# 15_-CLOCK.net
KiCad netlist of a schematic drawn in Altium Designer
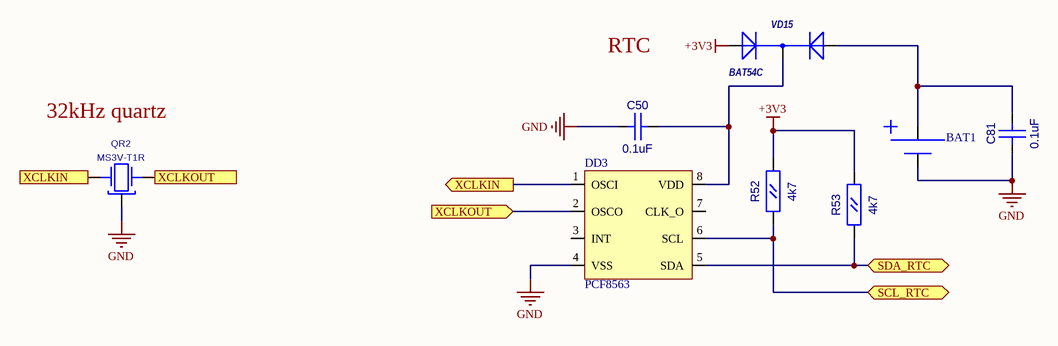
[diagram p0: [15]-CLOCK.SchDoc]

(export (version "E")
  (design (tool "Eeschema 10.0.6"))
  (components
    (comp (ref "BAT1")
      (value "CR2032-VBY4")
      (footprint "CR2032_ONBOARD")
      (libsource (lib "fizik_lib (1)") (part "CR2032-VBY2"))
    )
    (comp (ref "C50")
      (value "0.1uF")
      (footprint "CC0603")
      (description "CC0603")
      (libsource (lib "gprs_modem_2") (part "CC0603"))
    )
    (comp (ref "C81")
      (value "0.1uF")
      (footprint "CC0603")
      (description "CC0603")
      (libsource (lib "fizik_lib") (part "CC0603"))
    )
    (comp (ref "DD3") (value "PCF8563") (footprint "SO-8") (libsource (lib "gprs_modem") (part "PCF8563")))
    (comp (ref "QR2")
      (value "MS3V-T1R")
      (footprint "MS3V-T1R")
      (description "CRYSTAL_32768 Hz")
      (libsource (lib "gprs_modem") (part "MS3V-T1R"))
    )
    (comp (ref "R52")
      (value "4k7")
      (footprint "RC0603")
      (description "RC0603")
      (libsource (lib "gprs_modem_2") (part "RC0603"))
    )
    (comp (ref "R53")
      (value "4k7")
      (footprint "RC0603")
      (description "RC0603")
      (libsource (lib "gprs_modem_2") (part "RC0603"))
    )
    (comp (ref "VD15")
      (value "BAT54C")
      (footprint "SOT-23(123)")
      (libsource (lib "fizik_lib") (part "BAT54C"))
    )
  )
  (nets
    (net (code "1") (name "+3V3") (class "Default")
      (node (ref "R52") (pin "2") (pinfunction "B_2") (pintype "passive"))
      (node (ref "R53") (pin "2") (pinfunction "B_2") (pintype "passive"))
      (node (ref "VD15") (pin "1") (pinfunction "A_1") (pintype "passive"))
    )
    (net (code "2") (name "/SCL_RTC") (class "Default")
      (node (ref "DD3") (pin "6") (pinfunction "SCL_6") (pintype "passive"))
      (node (ref "R52") (pin "1") (pinfunction "A_1") (pintype "passive"))
    )
    (net (code "3") (name "/SDA_RTC") (class "Default")
      (node (ref "DD3") (pin "5") (pinfunction "SDA_5") (pintype "passive"))
      (node (ref "R53") (pin "1") (pinfunction "A_1") (pintype "passive"))
    )
    (net (code "4") (name "/XCLKIN") (class "Default")
      (node (ref "DD3") (pin "1") (pinfunction "OSCI_1") (pintype "passive"))
      (node (ref "QR2") (pin "2") (pinfunction "X2_2") (pintype "passive"))
    )
    (net (code "5") (name "/XCLKOUT") (class "Default")
      (node (ref "DD3") (pin "2") (pinfunction "OSCO_2") (pintype "passive"))
      (node (ref "QR2") (pin "1") (pinfunction "X1_1") (pintype "passive"))
    )
    (net (code "6") (name "GND") (class "Default")
      (node (ref "BAT1") (pin "1") (pintype "passive"))
      (node (ref "C50") (pin "1") (pinfunction "A_1") (pintype "passive"))
      (node (ref "C81") (pin "1") (pinfunction "A_1") (pintype "passive"))
      (node (ref "DD3") (pin "4") (pinfunction "VSS_4") (pintype "passive"))
      (node (ref "QR2") (pin "3") (pinfunction "3_3") (pintype "passive"))
    )
    (net (code "7") (name "Net-(C50-B)") (class "Default")
      (node (ref "C50") (pin "2") (pinfunction "B_2") (pintype "passive"))
      (node (ref "DD3") (pin "8") (pinfunction "VDD_8") (pintype "passive"))
      (node (ref "VD15") (pin "3") (pinfunction "K_3") (pintype "passive"))
    )
    (net (code "8") (name "Net-(C81-B)") (class "Default")
      (node (ref "BAT1") (pin "2") (pintype "passive"))
      (node (ref "C81") (pin "2") (pinfunction "B_2") (pintype "passive"))
      (node (ref "VD15") (pin "2") (pinfunction "A_2") (pintype "passive"))
    )
    (net (code "9") (name "unconnected-(DD3-CLK_O-Pad7)") (class "Default")
      (node (ref "DD3") (pin "7") (pinfunction "CLK_O_7") (pintype "passive"))
    )
    (net (code "10") (name "unconnected-(DD3-INT-Pad3)") (class "Default")
      (node (ref "DD3") (pin "3") (pinfunction "INT_3") (pintype "passive"))
    )
  )
)
